# OPA1622_-_Breakout.net
KiCad netlist of a schematic drawn in EAGLE
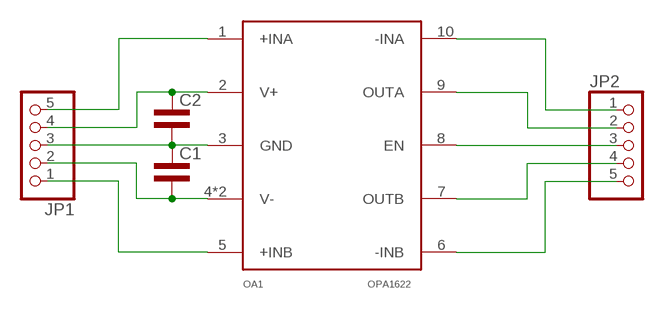
[diagram p0: schematic, sheet 1]

(export (version "E")
  (design (tool "Eeschema 10.0.6"))
  (components
    (comp (ref "C1")
      (value "CAP0603L3")
      (footprint "eagle-import:0603L3")
      (libsource (lib "eagle-import") (part "CAP0603L3"))
    )
    (comp (ref "C2")
      (value "CAP0603L3")
      (footprint "eagle-import:0603L3")
      (libsource (lib "eagle-import") (part "CAP0603L3"))
    )
    (comp (ref "JP1")
      (value "PINHD-1X5")
      (footprint "eagle-import:1X05")
      (libsource (lib "eagle-import") (part "PINHD-1X5"))
    )
    (comp (ref "JP2")
      (value "PINHD-1X5")
      (footprint "eagle-import:1X05")
      (libsource (lib "eagle-import") (part "PINHD-1X5"))
    )
    (comp (ref "OA1")
      (value "OPA1622")
      (footprint "eagle-import:S-PVSON-N10")
      (libsource (lib "eagle-import") (part "OPA1622"))
    )
  )
  (nets
    (net (code "1") (name "Net-(C1-1)") (class "Default")
      (node (ref "C1") (pin "P$1") (pinfunction "1_P$1") (pintype "bidirectional"))
      (node (ref "C2") (pin "P$2") (pinfunction "2_P$2") (pintype "bidirectional"))
      (node (ref "JP1") (pin "3") (pinfunction "3_3") (pintype "passive"))
      (node (ref "OA1") (pin "3") (pinfunction "GND_3") (pintype "bidirectional"))
    )
    (net (code "2") (name "Net-(C1-2)") (class "Default")
      (node (ref "C1") (pin "P$2") (pinfunction "2_P$2") (pintype "bidirectional"))
      (node (ref "JP1") (pin "2") (pinfunction "2_2") (pintype "passive"))
      (node (ref "OA1") (pin "4") (pinfunction "V-_4") (pintype "bidirectional"))
      (node (ref "OA1") (pin "TP") (pinfunction "V-_TP") (pintype "bidirectional"))
    )
    (net (code "3") (name "Net-(C2-1)") (class "Default")
      (node (ref "C2") (pin "P$1") (pinfunction "1_P$1") (pintype "bidirectional"))
      (node (ref "JP1") (pin "4") (pinfunction "4_4") (pintype "passive"))
      (node (ref "OA1") (pin "2") (pinfunction "V+_2") (pintype "bidirectional"))
    )
    (net (code "4") (name "Net-(OA1-+INA)") (class "Default")
      (node (ref "JP1") (pin "5") (pinfunction "5_5") (pintype "passive"))
      (node (ref "OA1") (pin "1") (pinfunction "+INA_1") (pintype "bidirectional"))
    )
    (net (code "5") (name "Net-(OA1-+INB)") (class "Default")
      (node (ref "JP1") (pin "1") (pinfunction "1_1") (pintype "passive"))
      (node (ref "OA1") (pin "5") (pinfunction "+INB_5") (pintype "bidirectional"))
    )
    (net (code "6") (name "Net-(OA1--INA)") (class "Default")
      (node (ref "JP2") (pin "1") (pinfunction "1_1") (pintype "passive"))
      (node (ref "OA1") (pin "10") (pinfunction "-INA_10") (pintype "bidirectional"))
    )
    (net (code "7") (name "Net-(OA1--INB)") (class "Default")
      (node (ref "JP2") (pin "5") (pinfunction "5_5") (pintype "passive"))
      (node (ref "OA1") (pin "6") (pinfunction "-INB_6") (pintype "bidirectional"))
    )
    (net (code "8") (name "Net-(OA1-EN)") (class "Default")
      (node (ref "JP2") (pin "3") (pinfunction "3_3") (pintype "passive"))
      (node (ref "OA1") (pin "8") (pinfunction "EN_8") (pintype "bidirectional"))
    )
    (net (code "9") (name "Net-(OA1-OUTA)") (class "Default")
      (node (ref "JP2") (pin "2") (pinfunction "2_2") (pintype "passive"))
      (node (ref "OA1") (pin "9") (pinfunction "OUTA_9") (pintype "bidirectional"))
    )
    (net (code "10") (name "Net-(OA1-OUTB)") (class "Default")
      (node (ref "JP2") (pin "4") (pinfunction "4_4") (pintype "passive"))
      (node (ref "OA1") (pin "7") (pinfunction "OUTB_7") (pintype "bidirectional"))
    )
  )
)
